# sim_reader.net
KiCad netlist of a schematic drawn in EAGLE
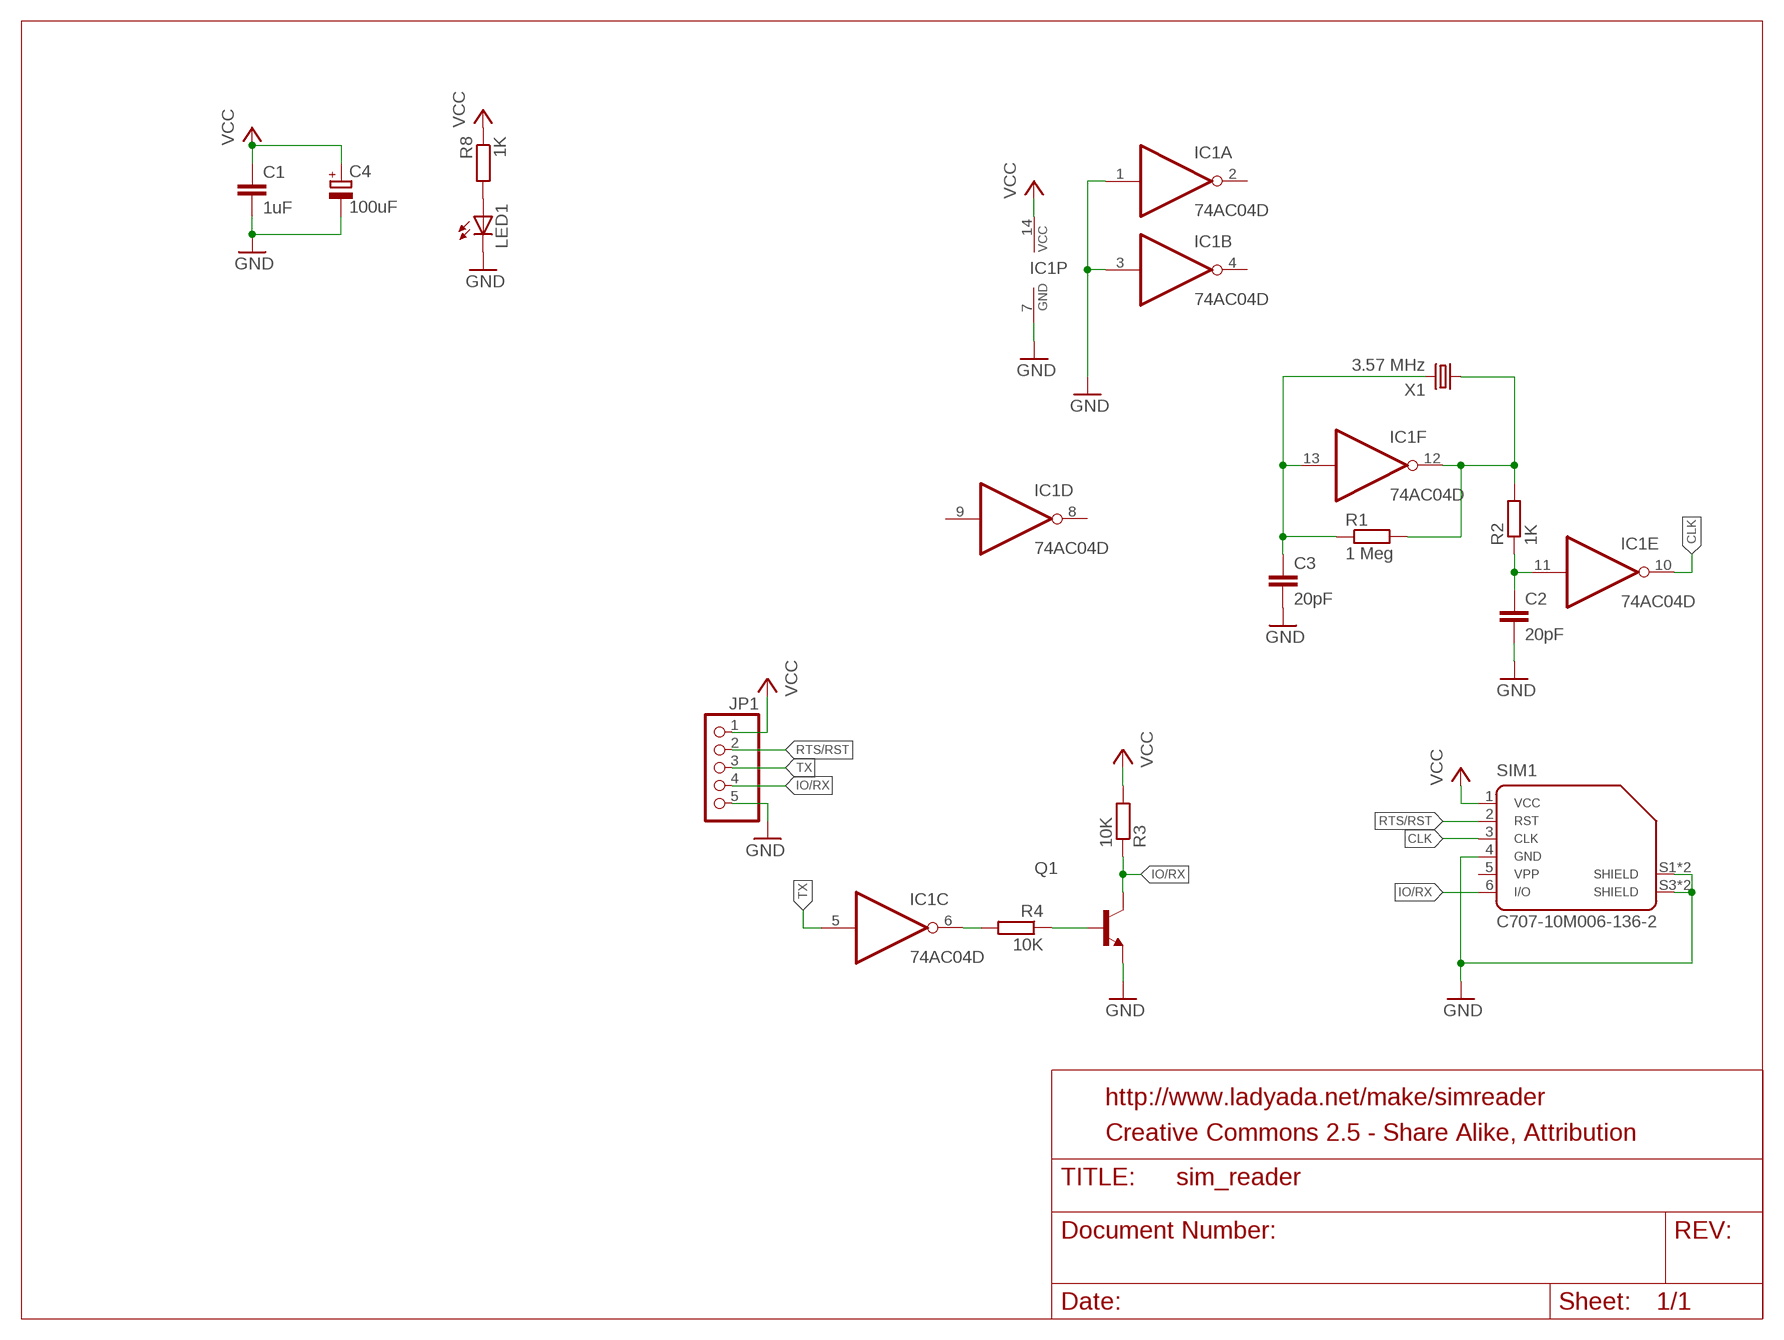
[diagram p0: schematic, sheet 1]

(export (version "E")
  (design (tool "Eeschema 10.0.6"))
  (components
    (comp (ref "C1")
      (value "1uF")
      (footprint "eagle-import:C0805")
      (libsource (lib "eagle-import") (part "C-EUC0805"))
    )
    (comp (ref "C2")
      (value "20pF")
      (footprint "eagle-import:C0805")
      (libsource (lib "eagle-import") (part "C-EUC0805"))
    )
    (comp (ref "C3")
      (value "20pF")
      (footprint "eagle-import:C0805")
      (libsource (lib "eagle-import") (part "C-EUC0805"))
    )
    (comp (ref "C4")
      (value "100uF")
      (footprint "eagle-import:140CLH-0810")
      (libsource (lib "eagle-import") (part "CPOL-EU140CLH-0810"))
    )
    (comp (ref "IC1")
      (value "74AC04D")
      (footprint "eagle-import:SO14")
      (libsource (lib "eagle-import") (part "7404DAC"))
    )
    (comp (ref "JP1")
      (value "PINHD-1X5")
      (footprint "eagle-import:1X05")
      (libsource (lib "eagle-import") (part "PINHD-1X5"))
    )
    (comp (ref "LED1")
      (value "LEDCHIPLED_0805")
      (footprint "eagle-import:CHIPLED_0805")
      (libsource (lib "eagle-import") (part "LEDCHIPLED_0805"))
    )
    (comp (ref "Q1")
      (value "BC808-NPN-SOT23-BEC")
      (footprint "eagle-import:SOT23-BEC")
      (libsource (lib "eagle-import") (part "-NPN-SOT23-BECBC808"))
    )
    (comp (ref "R1")
      (value "1 Meg")
      (footprint "eagle-import:R0805")
      (libsource (lib "eagle-import") (part "R-EU_R0805"))
    )
    (comp (ref "R2")
      (value "1K")
      (footprint "eagle-import:R0805")
      (libsource (lib "eagle-import") (part "R-EU_R0805"))
    )
    (comp (ref "R3")
      (value "10K")
      (footprint "eagle-import:R0805")
      (libsource (lib "eagle-import") (part "R-EU_R0805"))
    )
    (comp (ref "R4")
      (value "10K")
      (footprint "eagle-import:R0805")
      (libsource (lib "eagle-import") (part "R-EU_R0805"))
    )
    (comp (ref "R8")
      (value "1K")
      (footprint "eagle-import:R0805")
      (libsource (lib "eagle-import") (part "R-EU_R0805"))
    )
    (comp (ref "SIM1")
      (value "C707-10M006-136-2")
      (footprint "eagle-import:C707_10M006_136_2")
      (libsource (lib "eagle-import") (part "C707-10M006-136-2"))
    )
    (comp (ref "X1")
      (value "3.57 MHz")
      (footprint "eagle-import:HC49UP")
      (libsource (lib "eagle-import") (part "CRYSTALHC49UP"))
    )
  )
  (nets
    (net (code "1") (name "CLK") (class "Default")
      (node (ref "IC1") (pin "10") (pinfunction "O_10") (pintype "output"))
      (node (ref "SIM1") (pin "3") (pinfunction "3_3") (pintype "passive"))
    )
    (net (code "2") (name "GND") (class "Default")
      (node (ref "C1") (pin "2") (pinfunction "2_2") (pintype "passive"))
      (node (ref "C2") (pin "2") (pinfunction "2_2") (pintype "passive"))
      (node (ref "C3") (pin "2") (pinfunction "2_2") (pintype "passive"))
      (node (ref "C4") (pin "-") (pinfunction "-_-") (pintype "passive"))
      (node (ref "IC1") (pin "1") (pinfunction "I_1") (pintype "input"))
      (node (ref "IC1") (pin "3") (pinfunction "I_3") (pintype "input"))
      (node (ref "IC1") (pin "7") (pinfunction "GND_7") (pintype "power_in"))
      (node (ref "JP1") (pin "5") (pinfunction "5_5") (pintype "passive"))
      (node (ref "LED1") (pin "C") (pinfunction "C_C") (pintype "passive"))
      (node (ref "Q1") (pin "E") (pinfunction "E_E") (pintype "passive"))
      (node (ref "SIM1") (pin "4") (pinfunction "4_4") (pintype "passive"))
      (node (ref "SIM1") (pin "S1") (pinfunction "S1_S1") (pintype "passive"))
      (node (ref "SIM1") (pin "S2") (pinfunction "S1_S2") (pintype "passive"))
      (node (ref "SIM1") (pin "S3") (pinfunction "S2_S3") (pintype "passive"))
      (node (ref "SIM1") (pin "S4") (pinfunction "S2_S4") (pintype "passive"))
    )
    (net (code "3") (name "IO{slash}RX") (class "Default")
      (node (ref "JP1") (pin "4") (pinfunction "4_4") (pintype "passive"))
      (node (ref "Q1") (pin "C") (pinfunction "C_C") (pintype "passive"))
      (node (ref "R3") (pin "1") (pinfunction "1_1") (pintype "passive"))
      (node (ref "SIM1") (pin "6") (pinfunction "6_6") (pintype "passive"))
    )
    (net (code "4") (name "Net-(IC1C-O)") (class "Default")
      (node (ref "IC1") (pin "6") (pinfunction "O_6") (pintype "output"))
      (node (ref "R4") (pin "2") (pinfunction "2_2") (pintype "passive"))
    )
    (net (code "5") (name "Net-(IC1E-I)") (class "Default")
      (node (ref "C2") (pin "1") (pinfunction "1_1") (pintype "passive"))
      (node (ref "IC1") (pin "11") (pinfunction "I_11") (pintype "input"))
      (node (ref "R2") (pin "1") (pinfunction "1_1") (pintype "passive"))
    )
    (net (code "6") (name "Net-(IC1F-I)") (class "Default")
      (node (ref "C3") (pin "1") (pinfunction "1_1") (pintype "passive"))
      (node (ref "IC1") (pin "13") (pinfunction "I_13") (pintype "input"))
      (node (ref "R1") (pin "1") (pinfunction "1_1") (pintype "passive"))
      (node (ref "X1") (pin "2") (pinfunction "2_2") (pintype "passive"))
    )
    (net (code "7") (name "Net-(IC1F-O)") (class "Default")
      (node (ref "IC1") (pin "12") (pinfunction "O_12") (pintype "output"))
      (node (ref "R1") (pin "2") (pinfunction "2_2") (pintype "passive"))
      (node (ref "R2") (pin "2") (pinfunction "2_2") (pintype "passive"))
      (node (ref "X1") (pin "1") (pinfunction "1_1") (pintype "passive"))
    )
    (net (code "8") (name "Net-(LED1-PadA)") (class "Default")
      (node (ref "LED1") (pin "A") (pinfunction "A_A") (pintype "passive"))
      (node (ref "R8") (pin "2") (pinfunction "2_2") (pintype "passive"))
    )
    (net (code "9") (name "Net-(Q1-PadB)") (class "Default")
      (node (ref "Q1") (pin "B") (pinfunction "B_B") (pintype "passive"))
      (node (ref "R4") (pin "1") (pinfunction "1_1") (pintype "passive"))
    )
    (net (code "10") (name "RTS{slash}RST") (class "Default")
      (node (ref "JP1") (pin "2") (pinfunction "2_2") (pintype "passive"))
      (node (ref "SIM1") (pin "2") (pinfunction "2_2") (pintype "passive"))
    )
    (net (code "11") (name "TX") (class "Default")
      (node (ref "IC1") (pin "5") (pinfunction "I_5") (pintype "input"))
      (node (ref "JP1") (pin "3") (pinfunction "3_3") (pintype "passive"))
    )
    (net (code "12") (name "VCC") (class "Default")
      (node (ref "C1") (pin "1") (pinfunction "1_1") (pintype "passive"))
      (node (ref "C4") (pin "+") (pinfunction "+_+") (pintype "passive"))
      (node (ref "IC1") (pin "14") (pinfunction "VCC_14") (pintype "power_in"))
      (node (ref "JP1") (pin "1") (pinfunction "1_1") (pintype "passive"))
      (node (ref "R3") (pin "2") (pinfunction "2_2") (pintype "passive"))
      (node (ref "R8") (pin "1") (pinfunction "1_1") (pintype "passive"))
      (node (ref "SIM1") (pin "1") (pinfunction "1_1") (pintype "passive"))
    )
    (net (code "13") (name "unconnected-(IC1A-O-Pad2)") (class "Default")
      (node (ref "IC1") (pin "2") (pinfunction "O_2") (pintype "output"))
    )
    (net (code "14") (name "unconnected-(IC1B-O-Pad4)") (class "Default")
      (node (ref "IC1") (pin "4") (pinfunction "O_4") (pintype "output"))
    )
    (net (code "15") (name "unconnected-(IC1D-I-Pad9)") (class "Default")
      (node (ref "IC1") (pin "9") (pinfunction "I_9") (pintype "input"))
    )
    (net (code "16") (name "unconnected-(IC1D-O-Pad8)") (class "Default")
      (node (ref "IC1") (pin "8") (pinfunction "O_8") (pintype "output"))
    )
    (net (code "17") (name "unconnected-(SIM1-Pad5)") (class "Default")
      (node (ref "SIM1") (pin "5") (pinfunction "5_5") (pintype "passive"))
    )
  )
)
